# I2C-Buffer_Adapter.net
KiCad netlist of a schematic drawn in EAGLE
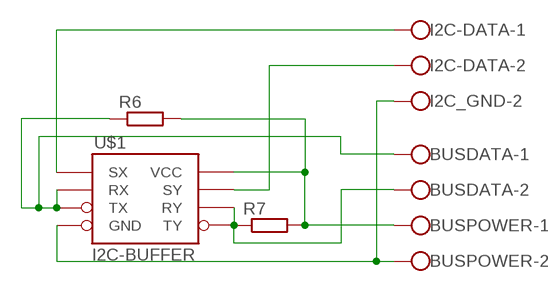
[diagram p0: schematic, sheet 1]

(export (version "E")
  (design (tool "Eeschema 10.0.6"))
  (components
    (comp (ref "BUSDATA")
      (value "W237-102")
      (footprint "eagle-import:W237-102")
      (fields (field (name "MPN") "237-102"))
      (libsource (lib "eagle-import") (part "W237-102"))
    )
    (comp (ref "BUSPOWER")
      (value "W237-102")
      (footprint "eagle-import:W237-102")
      (fields (field (name "MPN") "237-102"))
      (libsource (lib "eagle-import") (part "W237-102"))
    )
    (comp (ref "I2C-DATA")
      (value "W237-102")
      (footprint "eagle-import:W237-102")
      (fields (field (name "MPN") "237-102"))
      (libsource (lib "eagle-import") (part "W237-102"))
    )
    (comp (ref "I2C_GND")
      (value "W237-102")
      (footprint "eagle-import:W237-102")
      (fields (field (name "MPN") "237-102"))
      (libsource (lib "eagle-import") (part "W237-102"))
    )
    (comp (ref "R6")
      (value "R-EU_0207/12")
      (footprint "eagle-import:0207_12")
      (libsource (lib "eagle-import") (part "R-EU_0207/12"))
    )
    (comp (ref "R7")
      (value "R-EU_0207/12")
      (footprint "eagle-import:0207_12")
      (libsource (lib "eagle-import") (part "R-EU_0207/12"))
    )
    (comp (ref "U$1")
      (value "I2C-BUFFER")
      (footprint "eagle-import:I2C-BUFFER")
      (libsource (lib "eagle-import") (part "I2C-BUFFER"))
    )
  )
  (nets
    (net (code "1") (name "Net-(BUSDATAA-KL)") (class "Default")
      (node (ref "BUSDATA") (pin "1") (pinfunction "KL_1") (pintype "passive"))
      (node (ref "R6") (pin "1") (pinfunction "1_1") (pintype "passive"))
      (node (ref "U$1") (pin "2") (pinfunction "RX_2") (pintype "bidirectional"))
      (node (ref "U$1") (pin "3") (pinfunction "TX_3") (pintype "bidirectional"))
    )
    (net (code "2") (name "Net-(BUSDATAB-KL)") (class "Default")
      (node (ref "BUSDATA") (pin "2") (pinfunction "KL_2") (pintype "passive"))
      (node (ref "R7") (pin "1") (pinfunction "1_1") (pintype "passive"))
      (node (ref "U$1") (pin "5") (pinfunction "TY_5") (pintype "bidirectional"))
      (node (ref "U$1") (pin "6") (pinfunction "RY_6") (pintype "bidirectional"))
    )
    (net (code "3") (name "Net-(BUSPOWERA-KL)") (class "Default")
      (node (ref "BUSPOWER") (pin "1") (pinfunction "KL_1") (pintype "passive"))
      (node (ref "R6") (pin "2") (pinfunction "2_2") (pintype "passive"))
      (node (ref "R7") (pin "2") (pinfunction "2_2") (pintype "passive"))
      (node (ref "U$1") (pin "8") (pinfunction "VCC_8") (pintype "bidirectional"))
    )
    (net (code "4") (name "Net-(BUSPOWERB-KL)") (class "Default")
      (node (ref "BUSPOWER") (pin "2") (pinfunction "KL_2") (pintype "passive"))
      (node (ref "I2C_GND") (pin "2") (pinfunction "KL_2") (pintype "passive"))
      (node (ref "U$1") (pin "4") (pinfunction "GND_4") (pintype "bidirectional"))
    )
    (net (code "5") (name "Net-(I2C-DATAA-KL)") (class "Default")
      (node (ref "I2C-DATA") (pin "1") (pinfunction "KL_1") (pintype "passive"))
      (node (ref "U$1") (pin "1") (pinfunction "SX_1") (pintype "bidirectional"))
    )
    (net (code "6") (name "Net-(I2C-DATAB-KL)") (class "Default")
      (node (ref "I2C-DATA") (pin "2") (pinfunction "KL_2") (pintype "passive"))
      (node (ref "U$1") (pin "7") (pinfunction "SY_7") (pintype "bidirectional"))
    )
  )
)
